# Arduino__Connectors.net
KiCad netlist of a schematic drawn in Altium Designer
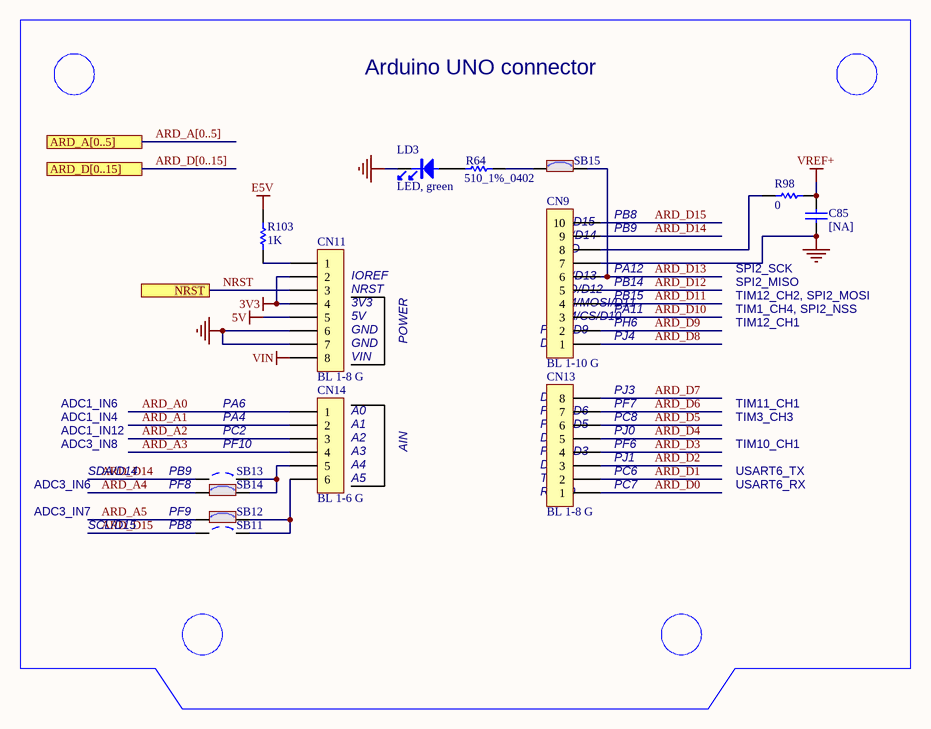
[diagram p0: Arduino_ Connectors.SchDoc]

(export (version "E")
  (design (tool "Eeschema 10.0.6"))
  (components
    (comp (ref "C85")
      (value "[NA]")
      (footprint "0402C")
      (description "Capacitor,NA,0402")
      (libsource (lib "MCD_TOOLS") (part "Cap_NA_0402"))
    )
    (comp (ref "CN9")
      (value "BL 1-10 G")
      (footprint "HDR_1X10_2R54_W")
      (description "Header, 10-Pin, Single row, female, THT, 2.54")
      (libsource (lib "MCD_TOOLS_CONNECTOR") (part "Header 10X1_Female_THT"))
    )
    (comp (ref "CN11")
      (value "BL 1-8 G")
      (footprint "HDR_1X8_2R54_W")
      (description "Header, 8-Pins, Single row, female, THT, 2.54")
      (libsource (lib "") (part "Header 8X1_Female_THT_1"))
    )
    (comp (ref "CN13")
      (value "BL 1-8 G")
      (footprint "HDR_1X8_2R54_W")
      (description "Header, 8-Pins, Single row, female, THT, 2.54")
      (libsource (lib "MCD_TOOLS_CONNECTOR") (part "Header 8X1_Female_THT"))
    )
    (comp (ref "CN14")
      (value "BL 1-6 G")
      (footprint "HDR_1X6_2R54_W")
      (description "Header, 6-Pins, Single row, female THT, 2.54")
      (libsource (lib "MCD_TOOLS_CONNECTOR") (part "Header 6X1_Female_THT"))
    )
    (comp (ref "LD3")
      (value "LED, green")
      (footprint "0603D")
      (description "LED, green, 0603")
      (libsource (lib "MCD_TOOLS") (part "LED_green"))
    )
    (comp (ref "R64")
      (value "510_1%_0402")
      (footprint "0402R")
      (description "Resistor,510,0402,1%,YAGEO")
      (libsource (lib "MCD_TOOLS") (part "Res_510_1%_0402"))
    )
    (comp (ref "R98")
      (value "0")
      (footprint "0402R")
      (description "Resistor,0,0402,5%,YAGEO")
      (libsource (lib "MCD_TOOLS") (part "Res_0_5%_0402"))
    )
    (comp (ref "R103")
      (value "1K")
      (footprint "0402R")
      (description "Resistor,1K,0402,1%,YAGEO")
      (libsource (lib "MCD_TOOLS_RESISTOR") (part "Res_1K_1%_0402"))
    )
    (comp (ref "SB11")
      (value "Solder Bridge OFF")
      (footprint "JP2_SMD")
      (libsource (lib "MCD_TOOLS") (part "SB_OFF"))
    )
    (comp (ref "SB12")
      (value "Solder Bridge ON")
      (footprint "JP2_SMD")
      (libsource (lib "MCD_TOOLS") (part "SB_ON"))
    )
    (comp (ref "SB13")
      (value "Solder Bridge OFF")
      (footprint "JP2_SMD")
      (libsource (lib "MCD_TOOLS") (part "SB_OFF"))
    )
    (comp (ref "SB14")
      (value "Solder Bridge ON")
      (footprint "JP2_SMD")
      (libsource (lib "MCD_TOOLS") (part "SB_ON"))
    )
    (comp (ref "SB15")
      (value "Solder Bridge ON")
      (footprint "JP2_SMD")
      (libsource (lib "MCD_TOOLS") (part "SB_ON"))
    )
  )
  (nets
    (net (code "1") (name "/ARD_A0") (class "Default")
      (node (ref "CN14") (pin "1") (pinfunction "1_1") (pintype "passive"))
    )
    (net (code "2") (name "/ARD_A1") (class "Default")
      (node (ref "CN14") (pin "2") (pinfunction "2_2") (pintype "passive"))
    )
    (net (code "3") (name "/ARD_A2") (class "Default")
      (node (ref "CN14") (pin "3") (pinfunction "3_3") (pintype "passive"))
    )
    (net (code "4") (name "/ARD_A3") (class "Default")
      (node (ref "CN14") (pin "4") (pinfunction "4_4") (pintype "passive"))
    )
    (net (code "5") (name "/ARD_A4") (class "Default")
      (node (ref "SB14") (pin "1") (pinfunction "1_1") (pintype "passive"))
    )
    (net (code "6") (name "/ARD_A5") (class "Default")
      (node (ref "SB12") (pin "1") (pinfunction "1_1") (pintype "passive"))
    )
    (net (code "8") (name "/ARD_D0") (class "Default")
      (node (ref "CN13") (pin "1") (pinfunction "1_1") (pintype "passive"))
    )
    (net (code "9") (name "/ARD_D1") (class "Default")
      (node (ref "CN13") (pin "2") (pinfunction "2_2") (pintype "passive"))
    )
    (net (code "10") (name "/ARD_D2") (class "Default")
      (node (ref "CN13") (pin "3") (pinfunction "3_3") (pintype "passive"))
    )
    (net (code "11") (name "/ARD_D3") (class "Default")
      (node (ref "CN13") (pin "4") (pinfunction "4_4") (pintype "passive"))
    )
    (net (code "12") (name "/ARD_D4") (class "Default")
      (node (ref "CN13") (pin "5") (pinfunction "5_5") (pintype "passive"))
    )
    (net (code "13") (name "/ARD_D5") (class "Default")
      (node (ref "CN13") (pin "6") (pinfunction "6_6") (pintype "passive"))
    )
    (net (code "14") (name "/ARD_D6") (class "Default")
      (node (ref "CN13") (pin "7") (pinfunction "7_7") (pintype "passive"))
    )
    (net (code "15") (name "/ARD_D7") (class "Default")
      (node (ref "CN13") (pin "8") (pinfunction "8_8") (pintype "passive"))
    )
    (net (code "16") (name "/ARD_D8") (class "Default")
      (node (ref "CN9") (pin "1") (pinfunction "1_1") (pintype "passive"))
    )
    (net (code "17") (name "/ARD_D9") (class "Default")
      (node (ref "CN9") (pin "2") (pinfunction "2_2") (pintype "passive"))
    )
    (net (code "18") (name "/ARD_D10") (class "Default")
      (node (ref "CN9") (pin "3") (pinfunction "3_3") (pintype "passive"))
    )
    (net (code "19") (name "/ARD_D11") (class "Default")
      (node (ref "CN9") (pin "4") (pinfunction "4_4") (pintype "passive"))
    )
    (net (code "20") (name "/ARD_D12") (class "Default")
      (node (ref "CN9") (pin "5") (pinfunction "5_5") (pintype "passive"))
    )
    (net (code "21") (name "/ARD_D13") (class "Default")
      (node (ref "CN9") (pin "6") (pinfunction "6_6") (pintype "passive"))
      (node (ref "SB15") (pin "2") (pinfunction "2_2") (pintype "passive"))
    )
    (net (code "22") (name "/ARD_D14") (class "Default")
      (node (ref "CN9") (pin "9") (pinfunction "9_9") (pintype "passive"))
      (node (ref "SB13") (pin "1") (pinfunction "1_1") (pintype "passive"))
    )
    (net (code "23") (name "/ARD_D15") (class "Default")
      (node (ref "CN9") (pin "10") (pinfunction "10_10") (pintype "passive"))
      (node (ref "SB11") (pin "1") (pinfunction "1_1") (pintype "passive"))
    )
    (net (code "25") (name "/NRST") (class "Default")
      (node (ref "CN11") (pin "3") (pinfunction "3_3") (pintype "passive"))
    )
    (net (code "26") (name "3V3") (class "Default")
      (node (ref "CN11") (pin "2") (pinfunction "2_2") (pintype "passive"))
      (node (ref "CN11") (pin "4") (pinfunction "4_4") (pintype "passive"))
    )
    (net (code "27") (name "5V") (class "Default")
      (node (ref "CN11") (pin "5") (pinfunction "5_5") (pintype "passive"))
    )
    (net (code "28") (name "E5V") (class "Default")
      (node (ref "R103") (pin "2") (pinfunction "2_2") (pintype "passive"))
    )
    (net (code "29") (name "GND") (class "Default")
      (node (ref "C85") (pin "1") (pinfunction "1_1") (pintype "passive"))
      (node (ref "CN11") (pin "6") (pinfunction "6_6") (pintype "passive"))
      (node (ref "CN11") (pin "7") (pinfunction "7_7") (pintype "passive"))
      (node (ref "CN9") (pin "7") (pinfunction "7_7") (pintype "passive"))
      (node (ref "LD3") (pin "2") (pintype "passive"))
    )
    (net (code "30") (name "Net-(CN9-Pad8)") (class "Default")
      (node (ref "CN9") (pin "8") (pinfunction "8_8") (pintype "passive"))
      (node (ref "R98") (pin "1") (pinfunction "1_1") (pintype "passive"))
    )
    (net (code "31") (name "Net-(CN11-Pad1)") (class "Default")
      (node (ref "CN11") (pin "1") (pinfunction "1_1") (pintype "passive"))
      (node (ref "R103") (pin "1") (pinfunction "1_1") (pintype "passive"))
    )
    (net (code "32") (name "Net-(CN14-Pad5)") (class "Default")
      (node (ref "CN14") (pin "5") (pinfunction "5_5") (pintype "passive"))
      (node (ref "SB13") (pin "2") (pinfunction "2_2") (pintype "passive"))
      (node (ref "SB14") (pin "2") (pinfunction "2_2") (pintype "passive"))
    )
    (net (code "33") (name "Net-(CN14-Pad6)") (class "Default")
      (node (ref "CN14") (pin "6") (pinfunction "6_6") (pintype "passive"))
      (node (ref "SB11") (pin "2") (pinfunction "2_2") (pintype "passive"))
      (node (ref "SB12") (pin "2") (pinfunction "2_2") (pintype "passive"))
    )
    (net (code "34") (name "Net-(LD3-Pad1)") (class "Default")
      (node (ref "LD3") (pin "1") (pintype "passive"))
      (node (ref "R64") (pin "1") (pinfunction "1_1") (pintype "passive"))
    )
    (net (code "35") (name "Net-(R64-Pad2)") (class "Default")
      (node (ref "R64") (pin "2") (pinfunction "2_2") (pintype "passive"))
      (node (ref "SB15") (pin "1") (pinfunction "1_1") (pintype "passive"))
    )
    (net (code "36") (name "VIN") (class "Default")
      (node (ref "CN11") (pin "8") (pinfunction "8_8") (pintype "passive"))
    )
    (net (code "37") (name "VREF+") (class "Default")
      (node (ref "C85") (pin "2") (pinfunction "2_2") (pintype "passive"))
      (node (ref "R98") (pin "2") (pinfunction "2_2") (pintype "passive"))
    )
  )
)
